# PCB_OnOnfre_SINGLE_rev1.net
KiCad netlist of a schematic drawn in EAGLE
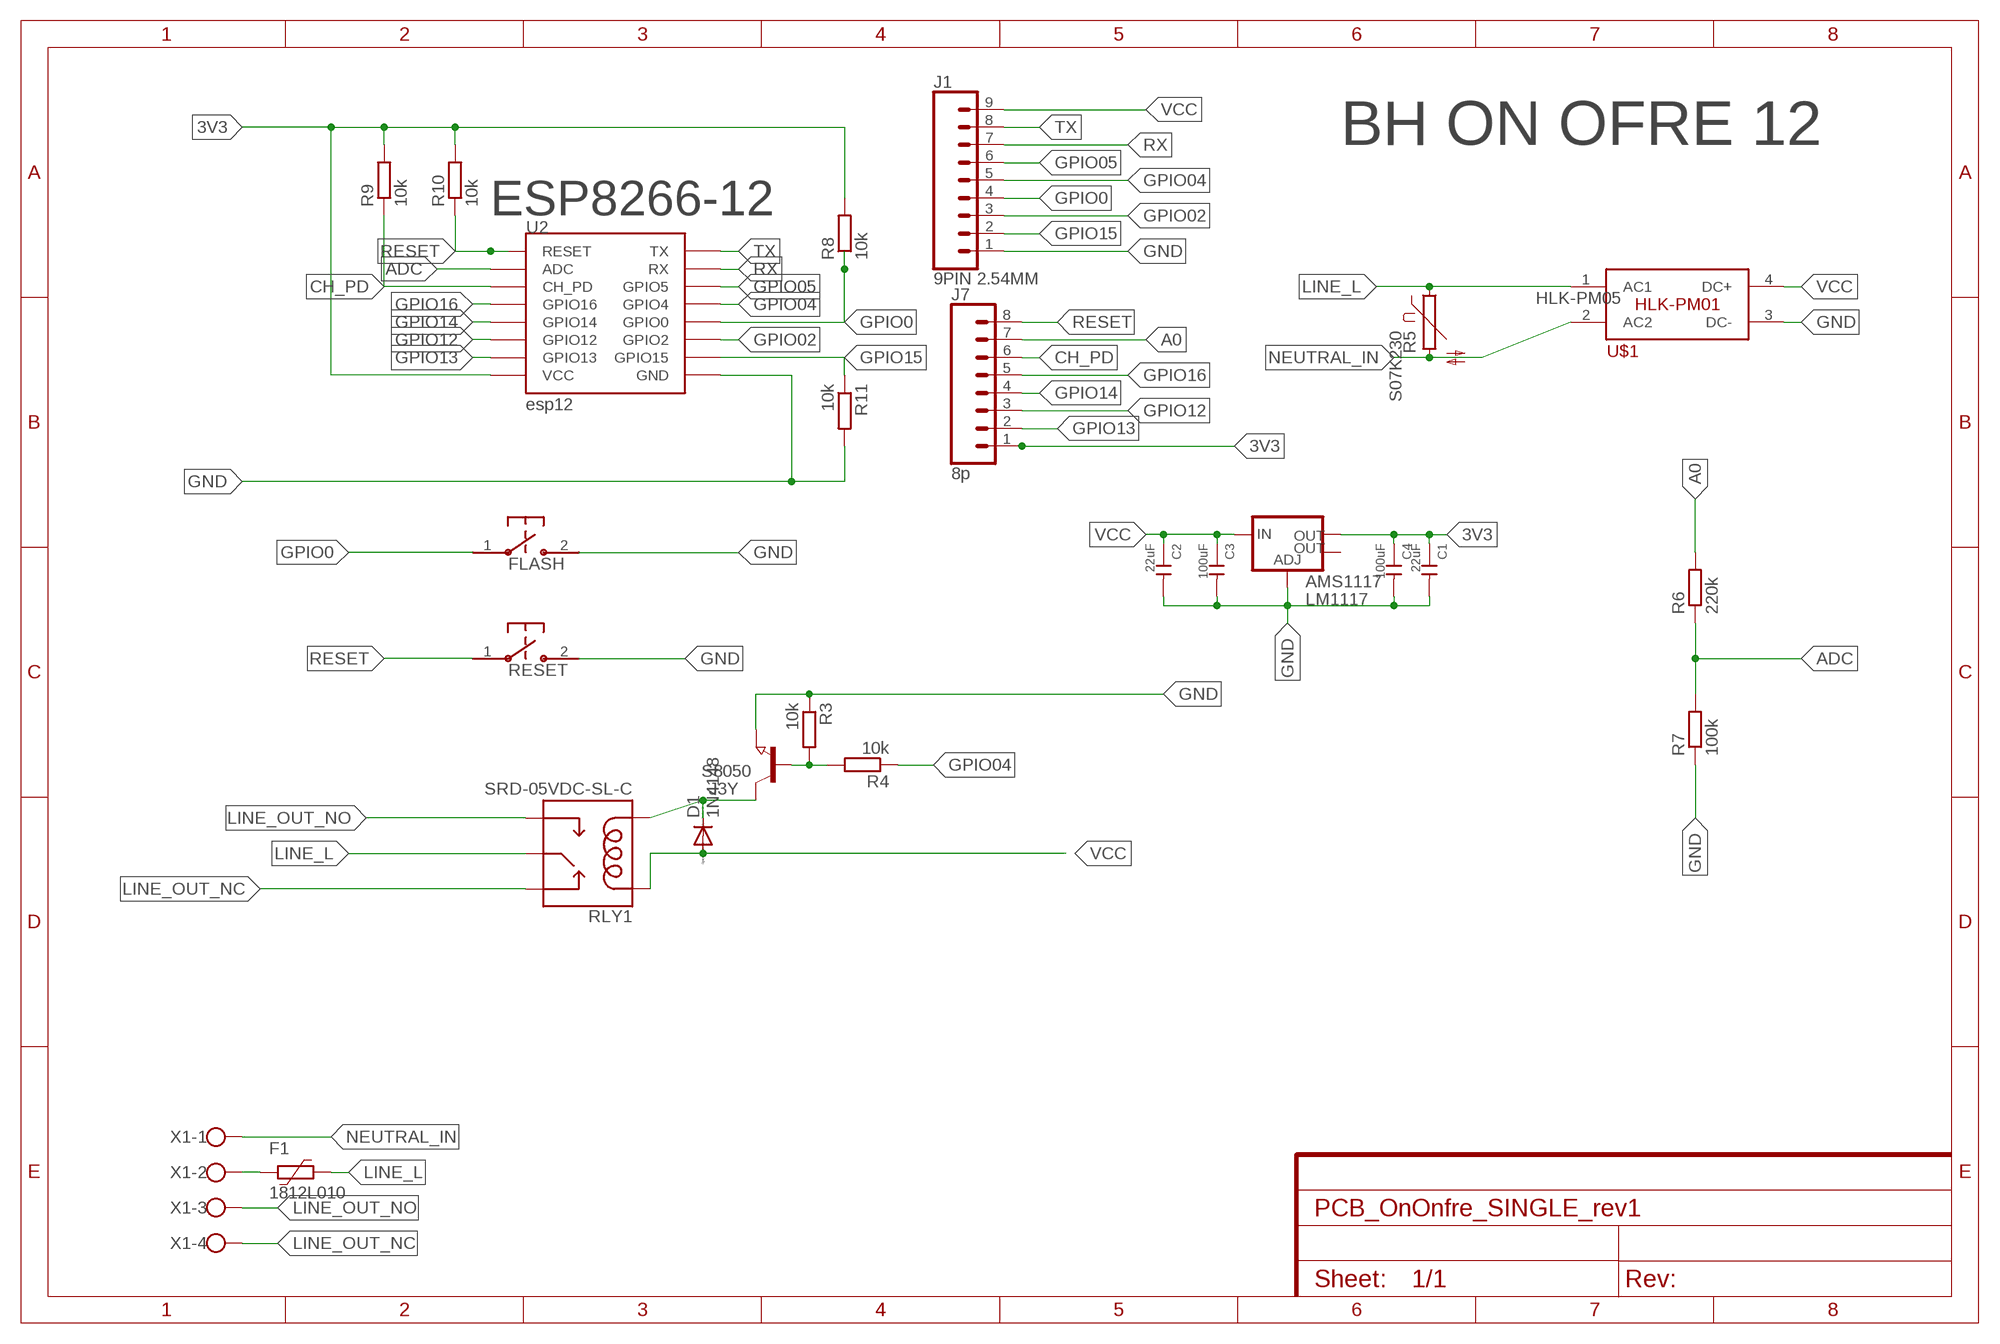
[diagram p0: schematic, sheet 1]

(export (version "E")
  (design (tool "Eeschema 10.0.6"))
  (components
    (comp (ref "AMS1117")
      (value "LM1117")
      (footprint "eagle-import:SOT223")
      (libsource (lib "eagle-import") (part "V_REG_LM1117SOT223"))
    )
    (comp (ref "C1")
      (value "22uF")
      (footprint "eagle-import:C1206")
      (fields (field (name "MPN") "CC1206KKX7RCBB102"))
      (libsource (lib "eagle-import") (part "CERAMIC-1NF-1KV-10%-X7R?(1206)"))
    )
    (comp (ref "C2")
      (value "22uF")
      (footprint "eagle-import:C1206")
      (fields (field (name "MPN") "CC1206KKX7RCBB102"))
      (libsource (lib "eagle-import") (part "CERAMIC-1NF-1KV-10%-X7R?(1206)"))
    )
    (comp (ref "C3")
      (value "100uF")
      (footprint "eagle-import:C1206")
      (fields (field (name "MPN") "CC1206KKX7RCBB102"))
      (libsource (lib "eagle-import") (part "CERAMIC-1NF-1KV-10%-X7R?(1206)"))
    )
    (comp (ref "C4")
      (value "100uF")
      (footprint "eagle-import:C1206")
      (fields (field (name "MPN") "CC1206KKX7RCBB102"))
      (libsource (lib "eagle-import") (part "CERAMIC-1NF-1KV-10%-X7R?(1206)"))
    )
    (comp (ref "D1")
      (value "1N4148")
      (footprint "eagle-import:SOD80C")
      (libsource (lib "eagle-import") (part "DIODE-SOD80C"))
    )
    (comp (ref "F1")
      (value "1812L010")
      (footprint "eagle-import:1812L")
      (fields (field (name "MF") "Littelfuse"))
      (libsource (lib "eagle-import") (part "?1812L010"))
    )
    (comp (ref "FLASH")
      (value "B3U-1000P-2P-SMD")
      (footprint "eagle-import:B3U-1000P")
      (fields (field (name "MANUFACTURER") "Omron") (field (name "MPN") "B3U-1000P"))
      (libsource (lib "eagle-import") (part "B3U-1000P"))
    )
    (comp (ref "J1")
      (value "9PIN 2.54MM")
      (footprint "eagle-import:1X09")
      (libsource (lib "eagle-import") (part "CONN_09"))
    )
    (comp (ref "J3Y")
      (value "S8050")
      (footprint "eagle-import:SOT23")
      (libsource (lib "eagle-import") (part "NPN-TRANSISTOR_SOT23"))
    )
    (comp (ref "J7")
      (value "8p")
      (footprint "eagle-import:1X08")
      (libsource (lib "eagle-import") (part "CONN_08{dblquote}"))
    )
    (comp (ref "R3")
      (value "10k")
      (footprint "eagle-import:R0603")
      (libsource (lib "eagle-import") (part "R-EU_R0603"))
    )
    (comp (ref "R4")
      (value "10k")
      (footprint "eagle-import:R0603")
      (libsource (lib "eagle-import") (part "R-EU_R0603"))
    )
    (comp (ref "R5")
      (value "S07K230")
      (footprint "eagle-import:S07K230")
      (libsource (lib "eagle-import") (part "S07K230"))
    )
    (comp (ref "R6")
      (value "220k")
      (footprint "eagle-import:R0603")
      (libsource (lib "eagle-import") (part "R-EU_R0603"))
    )
    (comp (ref "R7")
      (value "100k")
      (footprint "eagle-import:R0603")
      (libsource (lib "eagle-import") (part "R-EU_R0603"))
    )
    (comp (ref "R8")
      (value "10k")
      (footprint "eagle-import:R0603")
      (libsource (lib "eagle-import") (part "R-EU_R0603"))
    )
    (comp (ref "R9")
      (value "10k")
      (footprint "eagle-import:R0603")
      (libsource (lib "eagle-import") (part "R-EU_R0603"))
    )
    (comp (ref "R10")
      (value "10k")
      (footprint "eagle-import:R0603")
      (libsource (lib "eagle-import") (part "R-EU_R0603"))
    )
    (comp (ref "R11")
      (value "10k")
      (footprint "eagle-import:R0603")
      (libsource (lib "eagle-import") (part "R-EU_R0603"))
    )
    (comp (ref "RESET")
      (value "B3U-1000P-2P-SMD")
      (footprint "eagle-import:B3U-1000P")
      (fields (field (name "MANUFACTURER") "Omron") (field (name "MPN") "B3U-1000P"))
      (libsource (lib "eagle-import") (part "B3U-1000P"))
    )
    (comp (ref "RLY1")
      (value "SRD-05VDC-SL-C")
      (footprint "eagle-import:SRD-5VDC-SL-C")
      (libsource (lib "eagle-import") (part "RELAYSONGLE"))
    )
    (comp (ref "U$1")
      (value "HLK-PM01")
      (footprint "eagle-import:HLK-PM01")
      (fields (field (name "MF") "Hi-link") (field (name "MP") "hlk-pm01"))
      (libsource (lib "eagle-import") (part "HLK-PM01"))
    )
    (comp (ref "U2")
      (value "esp12")
      (footprint "eagle-import:ESP12-SMD")
      (libsource (lib "eagle-import") (part "ESP12SMD"))
    )
    (comp (ref "X1")
      (value "W237-4")
      (footprint "eagle-import:W237-4")
      (libsource (lib "eagle-import") (part "W237-4"))
    )
  )
  (nets
    (net (code "1") (name "3V3") (class "Default")
      (node (ref "AMS1117") (pin "2") (pinfunction "OUT_2") (pintype "output"))
      (node (ref "C1") (pin "1") (pinfunction "1_1") (pintype "passive"))
      (node (ref "C4") (pin "1") (pinfunction "1_1") (pintype "passive"))
      (node (ref "J7") (pin "1") (pinfunction "1_1") (pintype "passive"))
      (node (ref "R10") (pin "2") (pinfunction "2_2") (pintype "passive"))
      (node (ref "R8") (pin "2") (pinfunction "2_2") (pintype "passive"))
      (node (ref "R9") (pin "2") (pinfunction "2_2") (pintype "passive"))
      (node (ref "U2") (pin "VCC") (pinfunction "VCC_VCC") (pintype "bidirectional"))
    )
    (net (code "2") (name "A0") (class "Default")
      (node (ref "J7") (pin "7") (pinfunction "7_7") (pintype "passive"))
      (node (ref "R6") (pin "2") (pinfunction "2_2") (pintype "passive"))
    )
    (net (code "3") (name "ADC") (class "Default")
      (node (ref "R6") (pin "1") (pinfunction "1_1") (pintype "passive"))
      (node (ref "R7") (pin "2") (pinfunction "2_2") (pintype "passive"))
      (node (ref "U2") (pin "ADC") (pinfunction "ADC_ADC") (pintype "bidirectional"))
    )
    (net (code "4") (name "CH_PD") (class "Default")
      (node (ref "J7") (pin "6") (pinfunction "6_6") (pintype "passive"))
      (node (ref "R9") (pin "1") (pinfunction "1_1") (pintype "passive"))
      (node (ref "U2") (pin "CH_PD") (pinfunction "CH_PD_CH_PD") (pintype "bidirectional"))
    )
    (net (code "5") (name "GND") (class "Default")
      (node (ref "AMS1117") (pin "1") (pinfunction "ADJ_1") (pintype "input"))
      (node (ref "C1") (pin "2") (pinfunction "2_2") (pintype "passive"))
      (node (ref "C2") (pin "2") (pinfunction "2_2") (pintype "passive"))
      (node (ref "C3") (pin "2") (pinfunction "2_2") (pintype "passive"))
      (node (ref "C4") (pin "2") (pinfunction "2_2") (pintype "passive"))
      (node (ref "FLASH") (pin "2") (pinfunction "P$2_2") (pintype "passive"))
      (node (ref "J1") (pin "1") (pinfunction "1_1") (pintype "passive"))
      (node (ref "J3Y") (pin "2") (pinfunction "E_2") (pintype "passive"))
      (node (ref "R11") (pin "2") (pinfunction "2_2") (pintype "passive"))
      (node (ref "R3") (pin "1") (pinfunction "1_1") (pintype "passive"))
      (node (ref "R7") (pin "1") (pinfunction "1_1") (pintype "passive"))
      (node (ref "RESET") (pin "2") (pinfunction "P$2_2") (pintype "passive"))
      (node (ref "U$1") (pin "3") (pinfunction "DC-_3") (pintype "power_in"))
      (node (ref "U2") (pin "GND") (pinfunction "GND_GND") (pintype "bidirectional"))
    )
    (net (code "6") (name "GPIO0") (class "Default")
      (node (ref "FLASH") (pin "1") (pinfunction "P$1_1") (pintype "passive"))
      (node (ref "J1") (pin "4") (pinfunction "4_4") (pintype "passive"))
      (node (ref "R8") (pin "1") (pinfunction "1_1") (pintype "passive"))
      (node (ref "U2") (pin "GPIO0") (pinfunction "GPIO0_GPIO0") (pintype "bidirectional"))
    )
    (net (code "7") (name "GPIO02") (class "Default")
      (node (ref "J1") (pin "3") (pinfunction "3_3") (pintype "passive"))
      (node (ref "U2") (pin "GPIO2") (pinfunction "GPIO2_GPIO2") (pintype "bidirectional"))
    )
    (net (code "8") (name "GPIO04") (class "Default")
      (node (ref "J1") (pin "5") (pinfunction "5_5") (pintype "passive"))
      (node (ref "R4") (pin "1") (pinfunction "1_1") (pintype "passive"))
      (node (ref "U2") (pin "GPIO4") (pinfunction "GPIO4_GPIO4") (pintype "bidirectional"))
    )
    (net (code "9") (name "GPIO05") (class "Default")
      (node (ref "J1") (pin "6") (pinfunction "6_6") (pintype "passive"))
      (node (ref "U2") (pin "GPIO5") (pinfunction "GPIO5_GPIO5") (pintype "bidirectional"))
    )
    (net (code "10") (name "GPIO12") (class "Default")
      (node (ref "J7") (pin "3") (pinfunction "3_3") (pintype "passive"))
      (node (ref "U2") (pin "GPIO12") (pinfunction "GPIO12_GPIO12") (pintype "bidirectional"))
    )
    (net (code "11") (name "GPIO13") (class "Default")
      (node (ref "J7") (pin "2") (pinfunction "2_2") (pintype "passive"))
      (node (ref "U2") (pin "GPIO13") (pinfunction "GPIO13_GPIO13") (pintype "bidirectional"))
    )
    (net (code "12") (name "GPIO14") (class "Default")
      (node (ref "J7") (pin "4") (pinfunction "4_4") (pintype "passive"))
      (node (ref "U2") (pin "GPIO14") (pinfunction "GPIO14_GPIO14") (pintype "bidirectional"))
    )
    (net (code "13") (name "GPIO15") (class "Default")
      (node (ref "J1") (pin "2") (pinfunction "2_2") (pintype "passive"))
      (node (ref "R11") (pin "1") (pinfunction "1_1") (pintype "passive"))
      (node (ref "U2") (pin "GPIO15") (pinfunction "GPIO15_GPIO15") (pintype "bidirectional"))
    )
    (net (code "14") (name "GPIO16") (class "Default")
      (node (ref "J7") (pin "5") (pinfunction "5_5") (pintype "passive"))
      (node (ref "U2") (pin "GPIO16") (pinfunction "GPIO16_GPIO16") (pintype "bidirectional"))
    )
    (net (code "15") (name "LINE_L") (class "Default")
      (node (ref "F1") (pin "1") (pinfunction "1_1") (pintype "passive"))
      (node (ref "R5") (pin "1") (pinfunction "1_1") (pintype "passive"))
      (node (ref "RLY1") (pin "COMMON") (pinfunction "MAIN_COMMON") (pintype "bidirectional"))
      (node (ref "U$1") (pin "1") (pinfunction "AC1_1") (pintype "power_in"))
    )
    (net (code "16") (name "LINE_OUT_NC") (class "Default")
      (node (ref "RLY1") (pin "CLOSED") (pinfunction "NC_CLOSED") (pintype "bidirectional"))
      (node (ref "X1") (pin "4") (pinfunction "KL_4") (pintype "passive"))
    )
    (net (code "17") (name "LINE_OUT_NO") (class "Default")
      (node (ref "RLY1") (pin "OPEN") (pinfunction "NO_OPEN") (pintype "bidirectional"))
      (node (ref "X1") (pin "3") (pinfunction "KL_3") (pintype "passive"))
    )
    (net (code "18") (name "NEUTRAL_IN") (class "Default")
      (node (ref "R5") (pin "2") (pinfunction "2_2") (pintype "passive"))
      (node (ref "U$1") (pin "2") (pinfunction "AC2_2") (pintype "power_in"))
      (node (ref "X1") (pin "1") (pinfunction "KL_1") (pintype "passive"))
    )
    (net (code "19") (name "Net-(J3Y-B)") (class "Default")
      (node (ref "J3Y") (pin "1") (pinfunction "B_1") (pintype "passive"))
      (node (ref "R3") (pin "2") (pinfunction "2_2") (pintype "passive"))
      (node (ref "R4") (pin "2") (pinfunction "2_2") (pintype "passive"))
    )
    (net (code "20") (name "Net-(J3Y-C)") (class "Default")
      (node (ref "D1") (pin "C") (pinfunction "C_C") (pintype "passive"))
      (node (ref "J3Y") (pin "3") (pinfunction "C_3") (pintype "passive"))
      (node (ref "RLY1") (pin "COIL2") (pinfunction "COIL2_COIL2") (pintype "bidirectional"))
    )
    (net (code "21") (name "Net-(X1B-KL)") (class "Default")
      (node (ref "F1") (pin "2") (pinfunction "2_2") (pintype "passive"))
      (node (ref "X1") (pin "2") (pinfunction "KL_2") (pintype "passive"))
    )
    (net (code "22") (name "RESET") (class "Default")
      (node (ref "J7") (pin "8") (pinfunction "8_8") (pintype "passive"))
      (node (ref "R10") (pin "1") (pinfunction "1_1") (pintype "passive"))
      (node (ref "RESET") (pin "1") (pinfunction "P$1_1") (pintype "passive"))
      (node (ref "U2") (pin "RESET") (pinfunction "RESET_RESET") (pintype "bidirectional"))
    )
    (net (code "23") (name "RX") (class "Default")
      (node (ref "J1") (pin "7") (pinfunction "7_7") (pintype "passive"))
      (node (ref "U2") (pin "RXD0") (pinfunction "RX_RXD0") (pintype "bidirectional"))
    )
    (net (code "24") (name "TX") (class "Default")
      (node (ref "J1") (pin "8") (pinfunction "8_8") (pintype "passive"))
      (node (ref "U2") (pin "TXD0") (pinfunction "TX_TXD0") (pintype "bidirectional"))
    )
    (net (code "25") (name "VCC") (class "Default")
      (node (ref "AMS1117") (pin "3") (pinfunction "IN_3") (pintype "input"))
      (node (ref "C2") (pin "1") (pinfunction "1_1") (pintype "passive"))
      (node (ref "C3") (pin "1") (pinfunction "1_1") (pintype "passive"))
      (node (ref "D1") (pin "A") (pinfunction "A_A") (pintype "passive"))
      (node (ref "J1") (pin "9") (pinfunction "9_9") (pintype "passive"))
      (node (ref "RLY1") (pin "COIL1") (pinfunction "COIL1_COIL1") (pintype "bidirectional"))
      (node (ref "U$1") (pin "4") (pinfunction "DC+_4") (pintype "power_in"))
    )
    (net (code "26") (name "unconnected-(AMS1117-OUT-Pad4)") (class "Default")
      (node (ref "AMS1117") (pin "4") (pinfunction "OUT_4") (pintype "output"))
    )
  )
)
